# shield-i2c-santa.net
KiCad netlist of a schematic drawn in EAGLE
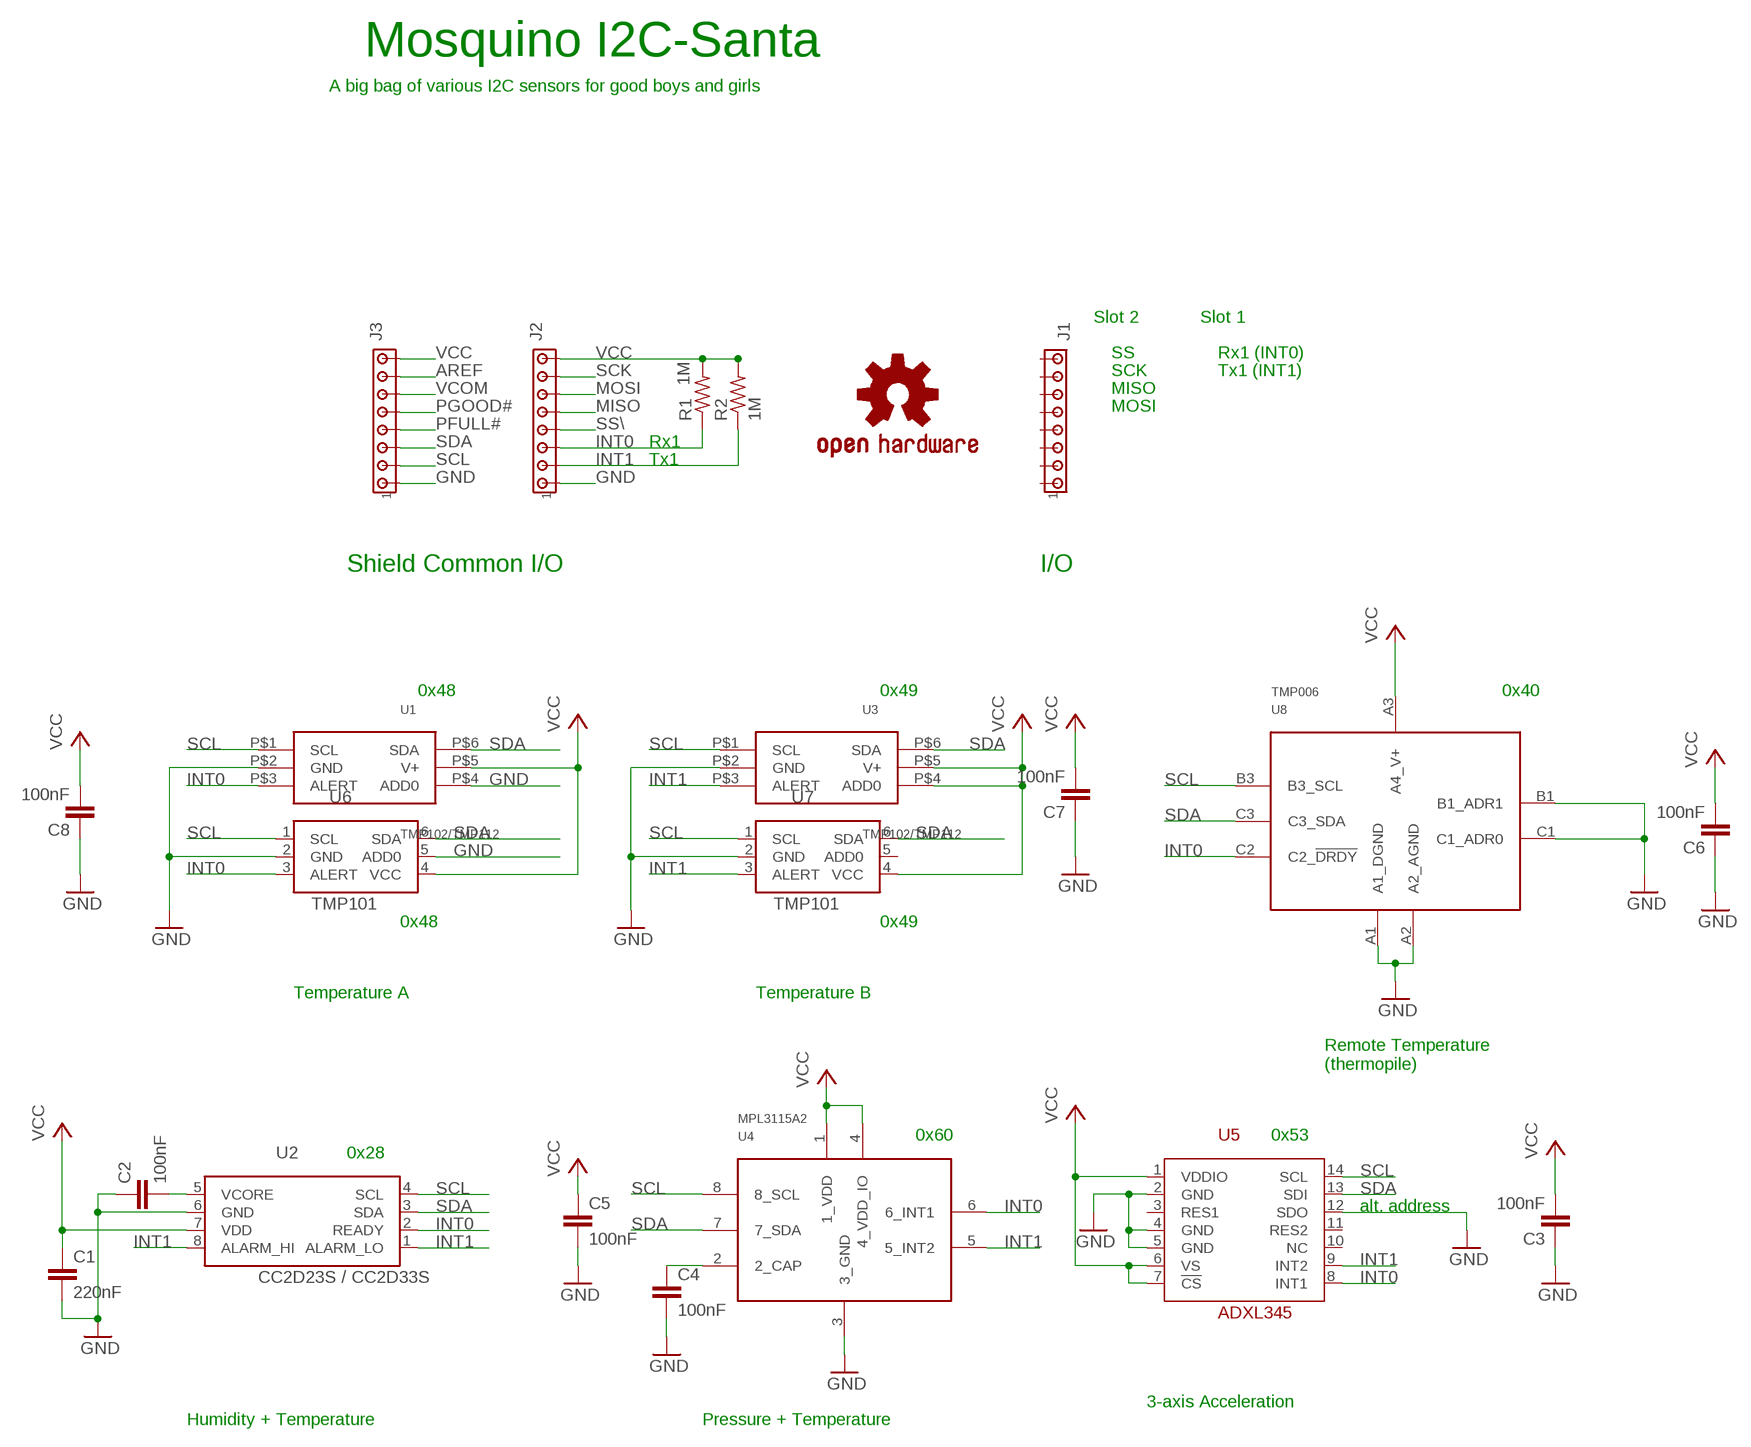
[diagram p0: schematic, sheet 1]

(export (version "E")
  (design (tool "Eeschema 10.0.6"))
  (components
    (comp (ref "C1")
      (value "220nF")
      (footprint "eagle-import:C0603")
      (libsource (lib "eagle-import") (part "C-EUC0603"))
    )
    (comp (ref "C2")
      (value "100nF")
      (footprint "eagle-import:C0603")
      (libsource (lib "eagle-import") (part "C-EUC0603"))
    )
    (comp (ref "C3")
      (value "100nF")
      (footprint "eagle-import:C0603")
      (libsource (lib "eagle-import") (part "C-EUC0603"))
    )
    (comp (ref "C4")
      (value "100nF")
      (footprint "eagle-import:C0603")
      (libsource (lib "eagle-import") (part "C-EUC0603"))
    )
    (comp (ref "C5")
      (value "100nF")
      (footprint "eagle-import:C0603")
      (libsource (lib "eagle-import") (part "C-EUC0603"))
    )
    (comp (ref "C6")
      (value "100nF")
      (footprint "eagle-import:C0603")
      (libsource (lib "eagle-import") (part "C-EUC0603"))
    )
    (comp (ref "C7")
      (value "100nF")
      (footprint "eagle-import:C0603")
      (libsource (lib "eagle-import") (part "C-EUC0603"))
    )
    (comp (ref "C8")
      (value "100nF")
      (footprint "eagle-import:C0603")
      (libsource (lib "eagle-import") (part "C-EUC0603"))
    )
    (comp (ref "J1")
      (value "MTA08-100")
      (footprint "eagle-import:10X08MTA")
      (libsource (lib "eagle-import") (part "MTA08-100"))
    )
    (comp (ref "J2")
      (value "MTA08-100")
      (footprint "eagle-import:10X08MTA")
      (libsource (lib "eagle-import") (part "MTA08-100"))
    )
    (comp (ref "J3")
      (value "MTA08-100")
      (footprint "eagle-import:10X08MTA")
      (libsource (lib "eagle-import") (part "MTA08-100"))
    )
    (comp (ref "LOGO1")
      (value "OSHW-LOGOS")
      (footprint "eagle-import:OSHW-LOGO-S")
      (libsource (lib "eagle-import") (part "OSHW-LOGOS"))
    )
    (comp (ref "R1")
      (value "1M")
      (footprint "eagle-import:R0603")
      (libsource (lib "eagle-import") (part "R-US_R0603"))
    )
    (comp (ref "R2")
      (value "1M")
      (footprint "eagle-import:R0603")
      (libsource (lib "eagle-import") (part "R-US_R0603"))
    )
    (comp (ref "U1")
      (value "TMP102/TMP112")
      (footprint "eagle-import:SOT563")
      (libsource (lib "eagle-import") (part "TMP102"))
    )
    (comp (ref "U2")
      (value "CC2D23S / CC2D33S")
      (footprint "eagle-import:CC2DXXX")
      (libsource (lib "eagle-import") (part "CC2DXXX"))
    )
    (comp (ref "U3")
      (value "TMP102/TMP112")
      (footprint "eagle-import:SOT563")
      (libsource (lib "eagle-import") (part "TMP102"))
    )
    (comp (ref "U4")
      (value "MPL3115A2")
      (footprint "eagle-import:8-LGA")
      (libsource (lib "eagle-import") (part "MPL3115A2"))
    )
    (comp (ref "U5")
      (value "ADXL345")
      (footprint "eagle-import:14-LGA")
      (libsource (lib "eagle-import") (part "ADXL345"))
    )
    (comp (ref "U6")
      (value "TMP101")
      (footprint "eagle-import:SOT23-6")
      (libsource (lib "eagle-import") (part "TMP101"))
    )
    (comp (ref "U7")
      (value "TMP101")
      (footprint "eagle-import:SOT23-6")
      (libsource (lib "eagle-import") (part "TMP101"))
    )
    (comp (ref "U8")
      (value "TMP006")
      (footprint "eagle-import:8-DSBGA")
      (libsource (lib "eagle-import") (part "TMP006"))
    )
  )
  (nets
    (net (code "1") (name "/AREF") (class "Default")
      (node (ref "J3") (pin "7") (pinfunction "7_7") (pintype "passive"))
    )
    (net (code "2") (name "/INT0") (class "Default")
      (node (ref "J2") (pin "3") (pinfunction "3_3") (pintype "passive"))
      (node (ref "R1") (pin "1") (pinfunction "1_1") (pintype "passive"))
      (node (ref "U1") (pin "P$3") (pinfunction "ALERT_P$3") (pintype "bidirectional"))
      (node (ref "U2") (pin "2") (pinfunction "READY_2") (pintype "bidirectional"))
      (node (ref "U4") (pin "6") (pinfunction "6_INT1_6") (pintype "output"))
      (node (ref "U5") (pin "8") (pinfunction "INT1_8") (pintype "bidirectional"))
      (node (ref "U6") (pin "3") (pinfunction "ALERT_3") (pintype "bidirectional"))
      (node (ref "U8") (pin "C2") (pinfunction "C2_~{DRDY}_C2") (pintype "bidirectional"))
    )
    (net (code "3") (name "/INT1") (class "Default")
      (node (ref "J2") (pin "2") (pinfunction "2_2") (pintype "passive"))
      (node (ref "R2") (pin "1") (pinfunction "1_1") (pintype "passive"))
      (node (ref "U2") (pin "1") (pinfunction "ALARM_LO_1") (pintype "bidirectional"))
      (node (ref "U2") (pin "8") (pinfunction "ALARM_HI_8") (pintype "bidirectional"))
      (node (ref "U3") (pin "P$3") (pinfunction "ALERT_P$3") (pintype "bidirectional"))
      (node (ref "U4") (pin "5") (pinfunction "5_INT2_5") (pintype "output"))
      (node (ref "U5") (pin "9") (pinfunction "INT2_9") (pintype "bidirectional"))
      (node (ref "U7") (pin "3") (pinfunction "ALERT_3") (pintype "bidirectional"))
    )
    (net (code "4") (name "/MISO") (class "Default")
      (node (ref "J2") (pin "5") (pinfunction "5_5") (pintype "passive"))
    )
    (net (code "5") (name "/MOSI") (class "Default")
      (node (ref "J2") (pin "6") (pinfunction "6_6") (pintype "passive"))
    )
    (net (code "6") (name "/PFULL#") (class "Default")
      (node (ref "J3") (pin "4") (pinfunction "4_4") (pintype "passive"))
    )
    (net (code "7") (name "/PGOOD#") (class "Default")
      (node (ref "J3") (pin "5") (pinfunction "5_5") (pintype "passive"))
    )
    (net (code "8") (name "/SCK") (class "Default")
      (node (ref "J2") (pin "7") (pinfunction "7_7") (pintype "passive"))
    )
    (net (code "9") (name "/SCL") (class "Default")
      (node (ref "J3") (pin "2") (pinfunction "2_2") (pintype "passive"))
      (node (ref "U1") (pin "P$1") (pinfunction "SCL_P$1") (pintype "bidirectional"))
      (node (ref "U2") (pin "4") (pinfunction "SCL_4") (pintype "bidirectional"))
      (node (ref "U3") (pin "P$1") (pinfunction "SCL_P$1") (pintype "bidirectional"))
      (node (ref "U4") (pin "8") (pinfunction "8_SCL_8") (pintype "input"))
      (node (ref "U5") (pin "14") (pinfunction "SCL_14") (pintype "bidirectional"))
      (node (ref "U6") (pin "1") (pinfunction "SCL_1") (pintype "bidirectional"))
      (node (ref "U7") (pin "1") (pinfunction "SCL_1") (pintype "bidirectional"))
      (node (ref "U8") (pin "B3") (pinfunction "B3_SCL_B3") (pintype "bidirectional"))
    )
    (net (code "10") (name "/SDA") (class "Default")
      (node (ref "J3") (pin "3") (pinfunction "3_3") (pintype "passive"))
      (node (ref "U1") (pin "P$6") (pinfunction "SDA_P$6") (pintype "bidirectional"))
      (node (ref "U2") (pin "3") (pinfunction "SDA_3") (pintype "bidirectional"))
      (node (ref "U3") (pin "P$6") (pinfunction "SDA_P$6") (pintype "bidirectional"))
      (node (ref "U4") (pin "7") (pinfunction "7_SDA_7") (pintype "bidirectional"))
      (node (ref "U5") (pin "13") (pinfunction "SDI_13") (pintype "bidirectional"))
      (node (ref "U6") (pin "6") (pinfunction "SDA_6") (pintype "bidirectional"))
      (node (ref "U7") (pin "6") (pinfunction "SDA_6") (pintype "bidirectional"))
      (node (ref "U8") (pin "C3") (pinfunction "C3_SDA_C3") (pintype "bidirectional"))
    )
    (net (code "11") (name "/SS\\") (class "Default")
      (node (ref "J2") (pin "4") (pinfunction "4_4") (pintype "passive"))
    )
    (net (code "12") (name "/VCOM") (class "Default")
      (node (ref "J3") (pin "6") (pinfunction "6_6") (pintype "passive"))
    )
    (net (code "13") (name "GND") (class "Default")
      (node (ref "C1") (pin "2") (pinfunction "2_2") (pintype "passive"))
      (node (ref "C2") (pin "1") (pinfunction "1_1") (pintype "passive"))
      (node (ref "C3") (pin "1") (pinfunction "1_1") (pintype "passive"))
      (node (ref "C4") (pin "2") (pinfunction "2_2") (pintype "passive"))
      (node (ref "C5") (pin "2") (pinfunction "2_2") (pintype "passive"))
      (node (ref "C6") (pin "1") (pinfunction "1_1") (pintype "passive"))
      (node (ref "C7") (pin "1") (pinfunction "1_1") (pintype "passive"))
      (node (ref "C8") (pin "1") (pinfunction "1_1") (pintype "passive"))
      (node (ref "J2") (pin "1") (pinfunction "1_1") (pintype "passive"))
      (node (ref "J3") (pin "1") (pinfunction "1_1") (pintype "passive"))
      (node (ref "U1") (pin "P$2") (pinfunction "GND_P$2") (pintype "power_in"))
      (node (ref "U1") (pin "P$4") (pinfunction "ADD0_P$4") (pintype "bidirectional"))
      (node (ref "U2") (pin "6") (pinfunction "GND_6") (pintype "power_in"))
      (node (ref "U3") (pin "P$2") (pinfunction "GND_P$2") (pintype "power_in"))
      (node (ref "U4") (pin "3") (pinfunction "3_GND_3") (pintype "power_in"))
      (node (ref "U5") (pin "12") (pinfunction "SDO_12") (pintype "bidirectional"))
      (node (ref "U5") (pin "2") (pinfunction "GND_2") (pintype "power_in"))
      (node (ref "U5") (pin "4") (pinfunction "GND_4") (pintype "power_in"))
      (node (ref "U5") (pin "5") (pinfunction "GND_5") (pintype "power_in"))
      (node (ref "U6") (pin "2") (pinfunction "GND_2") (pintype "power_in"))
      (node (ref "U6") (pin "5") (pinfunction "ADD0_5") (pintype "bidirectional"))
      (node (ref "U7") (pin "2") (pinfunction "GND_2") (pintype "power_in"))
      (node (ref "U8") (pin "A1") (pinfunction "A1_DGND_A1") (pintype "power_in"))
      (node (ref "U8") (pin "A2") (pinfunction "A2_AGND_A2") (pintype "power_in"))
      (node (ref "U8") (pin "B1") (pinfunction "B1_ADR1_B1") (pintype "bidirectional"))
      (node (ref "U8") (pin "C1") (pinfunction "C1_ADR0_C1") (pintype "bidirectional"))
    )
    (net (code "14") (name "Net-(U2-VCORE)") (class "Default")
      (node (ref "C2") (pin "2") (pinfunction "2_2") (pintype "passive"))
      (node (ref "U2") (pin "5") (pinfunction "VCORE_5") (pintype "bidirectional"))
    )
    (net (code "15") (name "Net-(U4-2_CAP)") (class "Default")
      (node (ref "C4") (pin "1") (pinfunction "1_1") (pintype "passive"))
      (node (ref "U4") (pin "2") (pinfunction "2_CAP_2") (pintype "passive"))
    )
    (net (code "16") (name "VCC") (class "Default")
      (node (ref "C1") (pin "1") (pinfunction "1_1") (pintype "passive"))
      (node (ref "C3") (pin "2") (pinfunction "2_2") (pintype "passive"))
      (node (ref "C5") (pin "1") (pinfunction "1_1") (pintype "passive"))
      (node (ref "C6") (pin "2") (pinfunction "2_2") (pintype "passive"))
      (node (ref "C7") (pin "2") (pinfunction "2_2") (pintype "passive"))
      (node (ref "C8") (pin "2") (pinfunction "2_2") (pintype "passive"))
      (node (ref "J2") (pin "8") (pinfunction "8_8") (pintype "passive"))
      (node (ref "J3") (pin "8") (pinfunction "8_8") (pintype "passive"))
      (node (ref "R1") (pin "2") (pinfunction "2_2") (pintype "passive"))
      (node (ref "R2") (pin "2") (pinfunction "2_2") (pintype "passive"))
      (node (ref "U1") (pin "P$5") (pinfunction "V+_P$5") (pintype "power_in"))
      (node (ref "U2") (pin "7") (pinfunction "VDD_7") (pintype "power_in"))
      (node (ref "U3") (pin "P$4") (pinfunction "ADD0_P$4") (pintype "bidirectional"))
      (node (ref "U3") (pin "P$5") (pinfunction "V+_P$5") (pintype "power_in"))
      (node (ref "U4") (pin "1") (pinfunction "1_VDD_1") (pintype "power_in"))
      (node (ref "U4") (pin "4") (pinfunction "4_VDD_IO_4") (pintype "power_in"))
      (node (ref "U5") (pin "1") (pinfunction "VDDIO_1") (pintype "power_in"))
      (node (ref "U5") (pin "6") (pinfunction "VS_6") (pintype "power_in"))
      (node (ref "U5") (pin "7") (pinfunction "~{CS}_7") (pintype "bidirectional"))
      (node (ref "U6") (pin "4") (pinfunction "VCC_4") (pintype "power_in"))
      (node (ref "U7") (pin "4") (pinfunction "VCC_4") (pintype "power_in"))
      (node (ref "U8") (pin "A3") (pinfunction "A4_V+_A3") (pintype "power_in"))
    )
    (net (code "17") (name "unconnected-(J1-Pad1)") (class "Default")
      (node (ref "J1") (pin "1") (pinfunction "1_1") (pintype "passive"))
    )
    (net (code "18") (name "unconnected-(J1-Pad2)") (class "Default")
      (node (ref "J1") (pin "2") (pinfunction "2_2") (pintype "passive"))
    )
    (net (code "19") (name "unconnected-(J1-Pad3)") (class "Default")
      (node (ref "J1") (pin "3") (pinfunction "3_3") (pintype "passive"))
    )
    (net (code "20") (name "unconnected-(J1-Pad4)") (class "Default")
      (node (ref "J1") (pin "4") (pinfunction "4_4") (pintype "passive"))
    )
    (net (code "21") (name "unconnected-(J1-Pad5)") (class "Default")
      (node (ref "J1") (pin "5") (pinfunction "5_5") (pintype "passive"))
    )
    (net (code "22") (name "unconnected-(J1-Pad6)") (class "Default")
      (node (ref "J1") (pin "6") (pinfunction "6_6") (pintype "passive"))
    )
    (net (code "23") (name "unconnected-(J1-Pad7)") (class "Default")
      (node (ref "J1") (pin "7") (pinfunction "7_7") (pintype "passive"))
    )
    (net (code "24") (name "unconnected-(J1-Pad8)") (class "Default")
      (node (ref "J1") (pin "8") (pinfunction "8_8") (pintype "passive"))
    )
    (net (code "25") (name "unconnected-(U5-NC-Pad10)") (class "Default")
      (node (ref "U5") (pin "10") (pinfunction "NC_10") (pintype "bidirectional"))
    )
    (net (code "26") (name "unconnected-(U5-RES1-Pad3)") (class "Default")
      (node (ref "U5") (pin "3") (pinfunction "RES1_3") (pintype "bidirectional"))
    )
    (net (code "27") (name "unconnected-(U5-RES2-Pad11)") (class "Default")
      (node (ref "U5") (pin "11") (pinfunction "RES2_11") (pintype "bidirectional"))
    )
    (net (code "28") (name "unconnected-(U7-ADD0-Pad5)") (class "Default")
      (node (ref "U7") (pin "5") (pinfunction "ADD0_5") (pintype "bidirectional"))
    )
  )
)
